# final_sensor_sch.net
KiCad netlist of a schematic drawn in Altium Designer
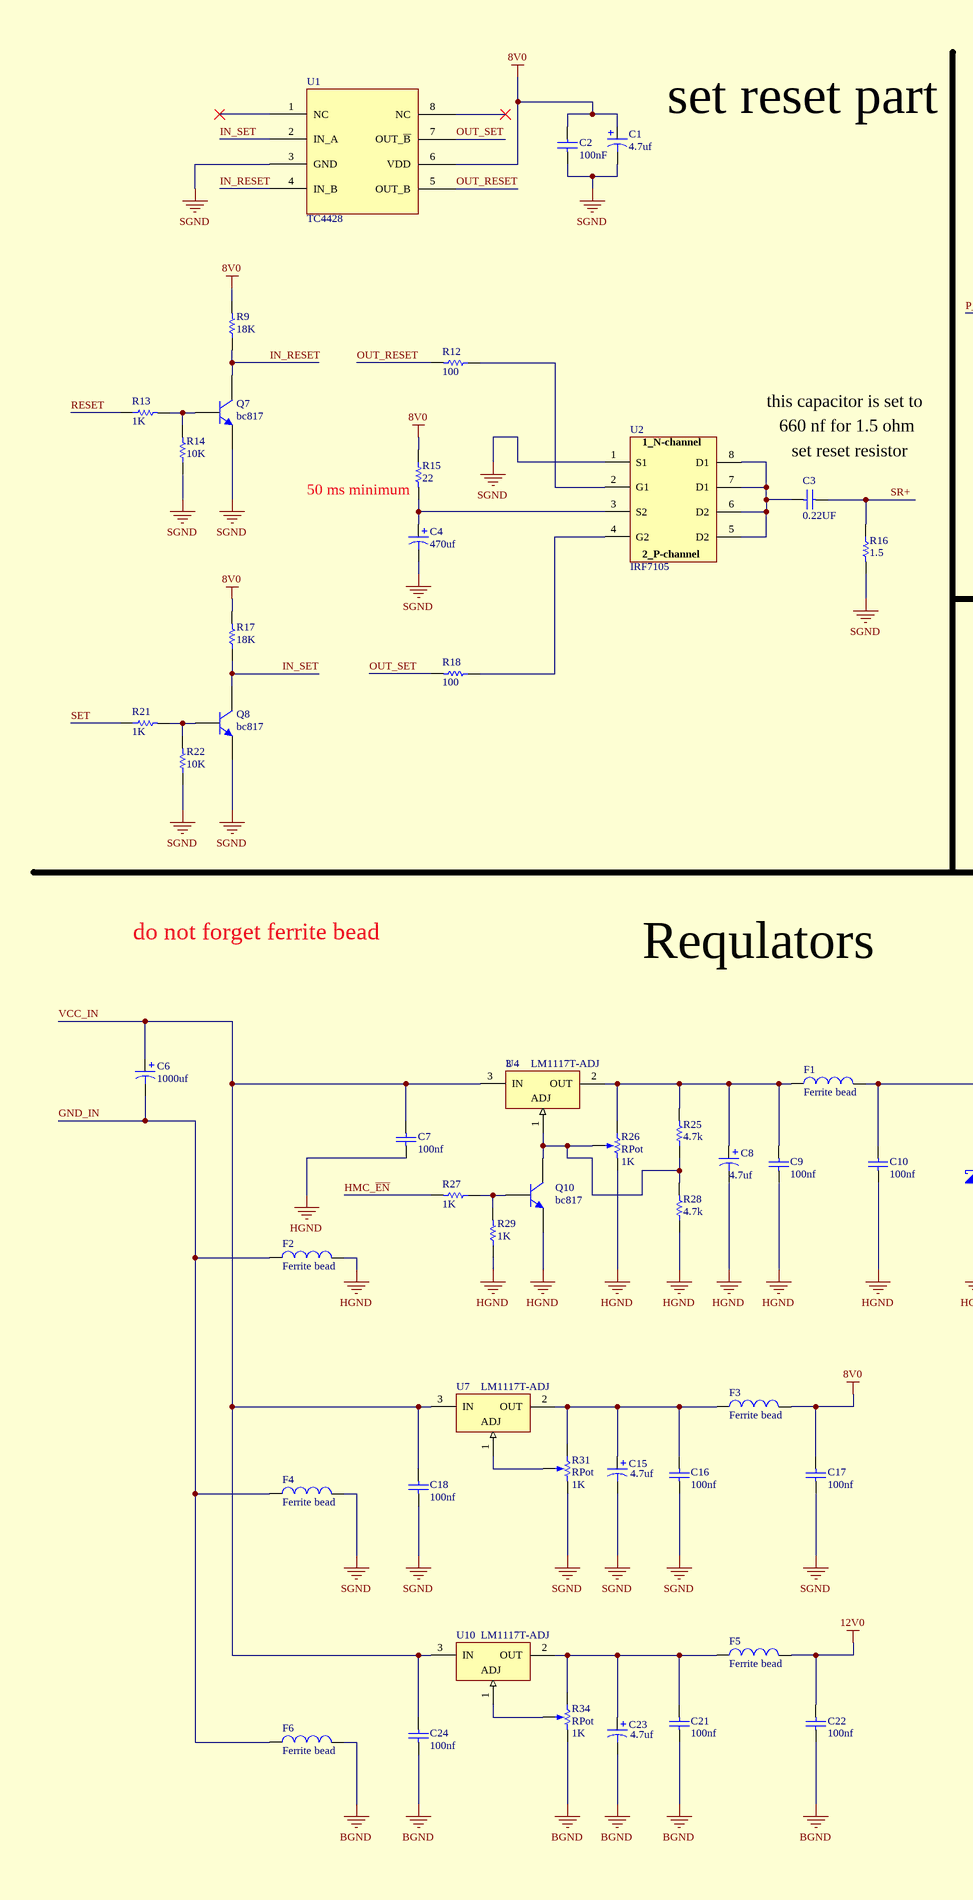
[diagram p0: final_sensor_sch.SchDoc, left]
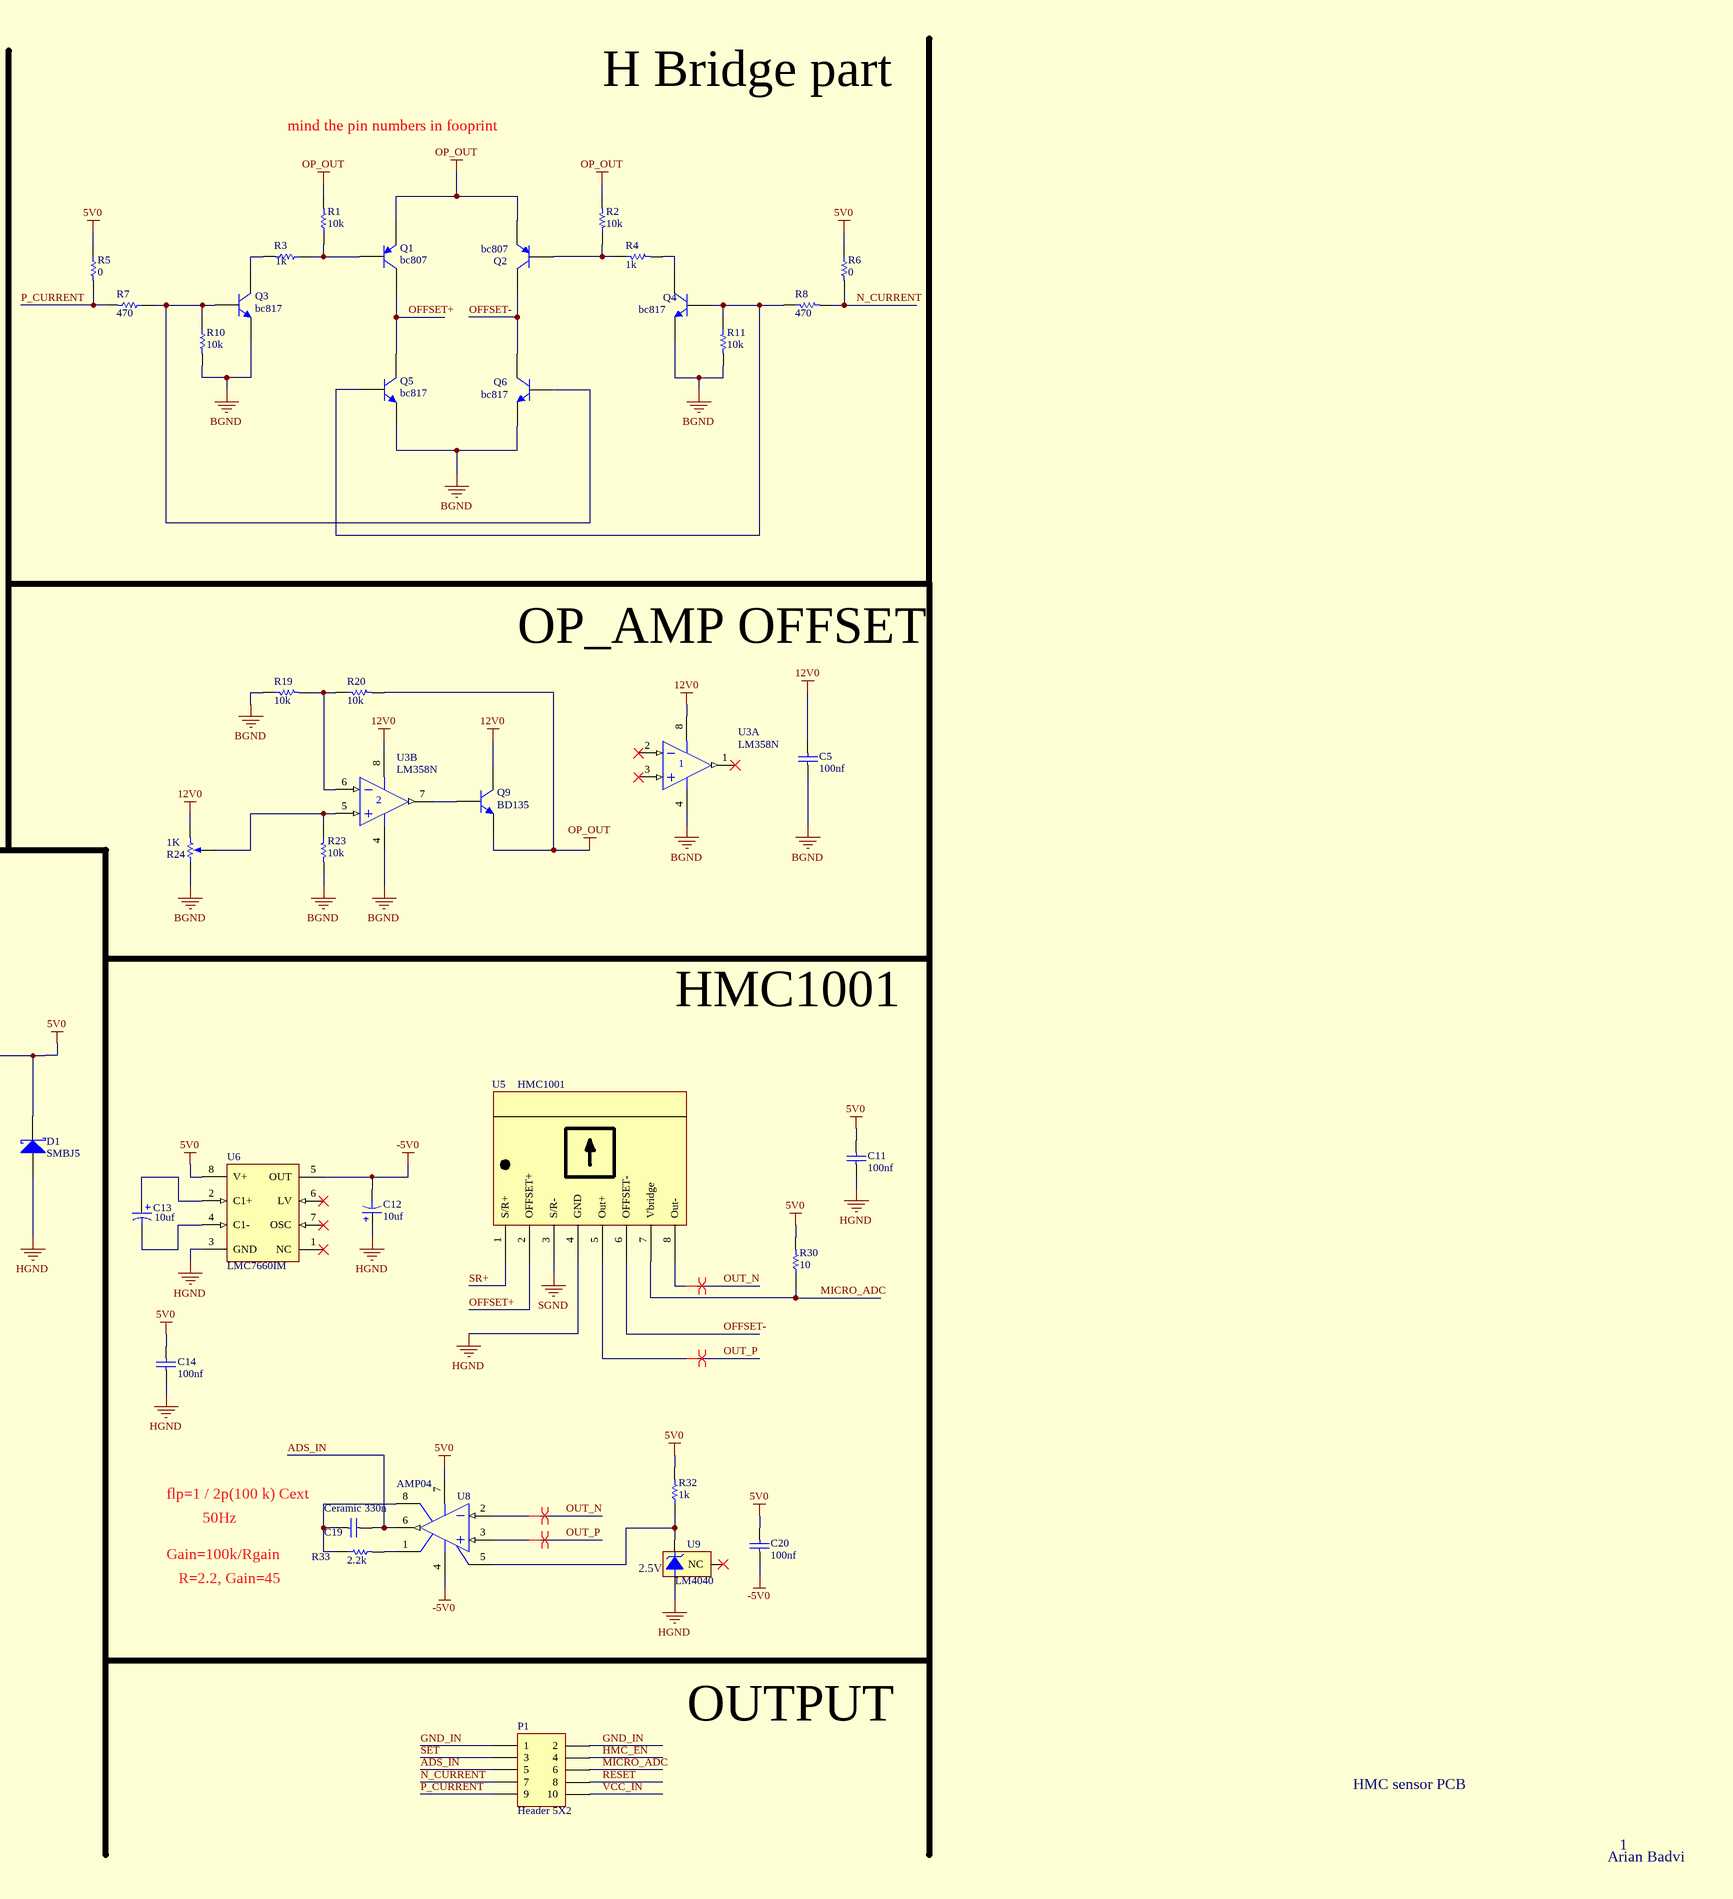
[diagram p1: final_sensor_sch.SchDoc, right]

(export (version "E")
  (design (tool "Eeschema 10.0.6"))
  (components
    (comp (ref "C1")
      (value "4.7uf")
      (footprint "cap_smd_a")
      (description "Polarized Capacitor (Radial)")
      (fields (field (name "PUBLISHER") "Altium Limited"))
      (libsource (lib "") (part "Cap Pol1_1"))
    )
    (comp (ref "C2")
      (value "100nF")
      (footprint "1206")
      (description "Capacitor")
      (fields (field (name "PUBLISHER") "Altium Limited"))
      (libsource (lib "Miscellaneous Devices") (part "Cap"))
    )
    (comp (ref "C3")
      (value "0.22UF")
      (footprint "1206")
      (description "Capacitor")
      (fields (field (name "PUBLISHER") "Altium Limited"))
      (libsource (lib "Miscellaneous Devices") (part "Cap"))
    )
    (comp (ref "C4")
      (value "470uf")
      (footprint "cap_smd_d")
      (description "Polarized Capacitor (Radial)")
      (fields (field (name "PUBLISHER") "Altium Limited"))
      (libsource (lib "Miscellaneous Devices") (part "Cap Pol1"))
    )
    (comp (ref "C5")
      (value "100nf")
      (footprint "1206")
      (description "Capacitor")
      (fields (field (name "PUBLISHER") "Altium Limited"))
      (libsource (lib "Miscellaneous Devices") (part "Cap"))
    )
    (comp (ref "C6")
      (value "1000uf")
      (footprint "c_cyl_smd")
      (description "electrolytic smd cap")
      (fields (field (name "PUBLISHER") "Altium Limited"))
      (libsource (lib "Miscellaneous Devices") (part "Cap Pol1"))
    )
    (comp (ref "C7")
      (value "100nf")
      (footprint "1206")
      (description "Capacitor")
      (fields (field (name "PUBLISHER") "Altium Limited"))
      (libsource (lib "Miscellaneous Devices") (part "Cap"))
    )
    (comp (ref "C8")
      (value "4.7uf")
      (footprint "cap_smd_a")
      (description "Polarized Capacitor (Radial)")
      (fields (field (name "PUBLISHER") "Altium Limited"))
      (libsource (lib "Miscellaneous Devices") (part "Cap Pol1"))
    )
    (comp (ref "C9")
      (value "100nf")
      (footprint "1206")
      (description "Capacitor")
      (fields (field (name "PUBLISHER") "Altium Limited"))
      (libsource (lib "Miscellaneous Devices") (part "Cap"))
    )
    (comp (ref "C10")
      (value "100nf")
      (footprint "1206")
      (description "Capacitor")
      (fields (field (name "PUBLISHER") "Altium Limited"))
      (libsource (lib "Miscellaneous Devices") (part "Cap"))
    )
    (comp (ref "C11")
      (value "100nf")
      (footprint "1206")
      (description "Capacitor")
      (fields (field (name "PUBLISHER") "Altium Limited"))
      (libsource (lib "Miscellaneous Devices") (part "Cap"))
    )
    (comp (ref "C12")
      (value "10uf")
      (footprint "cap_smd_a")
      (description "Polarized Capacitor (Radial)")
      (fields (field (name "PUBLISHER") "Altium Limited"))
      (libsource (lib "Miscellaneous Devices") (part "Cap Pol1"))
    )
    (comp (ref "C13")
      (value "10uf")
      (footprint "cap_smd_a")
      (description "Polarized Capacitor (Radial)")
      (fields (field (name "PUBLISHER") "Altium Limited"))
      (libsource (lib "Miscellaneous Devices") (part "Cap Pol1"))
    )
    (comp (ref "C14")
      (value "100nf")
      (footprint "1206")
      (description "Capacitor")
      (fields (field (name "PUBLISHER") "Altium Limited"))
      (libsource (lib "Miscellaneous Devices") (part "Cap"))
    )
    (comp (ref "C15")
      (value "4.7uf")
      (footprint "cap_smd_a")
      (description "Polarized Capacitor (Radial)")
      (fields (field (name "PUBLISHER") "Altium Limited"))
      (libsource (lib "Miscellaneous Devices") (part "Cap Pol1"))
    )
    (comp (ref "C16")
      (value "100nf")
      (footprint "1206")
      (description "Capacitor")
      (fields (field (name "PUBLISHER") "Altium Limited"))
      (libsource (lib "Miscellaneous Devices") (part "Cap"))
    )
    (comp (ref "C17")
      (value "100nf")
      (footprint "1206")
      (description "Capacitor")
      (fields (field (name "PUBLISHER") "Altium Limited"))
      (libsource (lib "Miscellaneous Devices") (part "Cap"))
    )
    (comp (ref "C18")
      (value "100nf")
      (footprint "1206")
      (description "Capacitor")
      (fields (field (name "PUBLISHER") "Altium Limited"))
      (libsource (lib "Miscellaneous Devices") (part "Cap"))
    )
    (comp (ref "C19")
      (value "Ceramic 330n")
      (footprint "1206")
      (description "Capacitor")
      (fields (field (name "PUBLISHER") "Altium Limited"))
      (libsource (lib "Library") (part "Cap"))
    )
    (comp (ref "C20")
      (value "100nf")
      (footprint "1206")
      (description "Capacitor")
      (fields (field (name "PUBLISHER") "Altium Limited"))
      (libsource (lib "Miscellaneous Devices") (part "Cap"))
    )
    (comp (ref "C21")
      (value "100nf")
      (footprint "1206")
      (description "Capacitor")
      (fields (field (name "PUBLISHER") "Altium Limited"))
      (libsource (lib "Miscellaneous Devices") (part "Cap"))
    )
    (comp (ref "C22")
      (value "100nf")
      (footprint "1206")
      (description "Capacitor")
      (fields (field (name "PUBLISHER") "Altium Limited"))
      (libsource (lib "Miscellaneous Devices") (part "Cap"))
    )
    (comp (ref "C23")
      (value "4.7uf")
      (footprint "cap_smd_a")
      (description "Polarized Capacitor (Radial)")
      (fields (field (name "PUBLISHER") "Altium Limited"))
      (libsource (lib "Miscellaneous Devices") (part "Cap Pol1"))
    )
    (comp (ref "C24")
      (value "100nf")
      (footprint "1206")
      (description "Capacitor")
      (fields (field (name "PUBLISHER") "Altium Limited"))
      (libsource (lib "Miscellaneous Devices") (part "Cap"))
    )
    (comp (ref "D1")
      (value "SMBJ5")
      (footprint "tvs")
      (description "tvs")
      (fields (field (name "PUBLISHER") "Altium Limited"))
      (libsource (lib "Miscellaneous Devices") (part "Diode 10TQ040"))
    )
    (comp (ref "F1")
      (value "Ferrite bead")
      (footprint "1206")
      (description "Ferrite bead, 1206")
      (fields (field (name "PUBLISHER") "Altium Limited"))
      (libsource (lib "Miscellaneous Devices") (part "Inductor"))
    )
    (comp (ref "F2")
      (value "Ferrite bead")
      (footprint "1206")
      (description "Ferrite bead, 1206")
      (fields (field (name "PUBLISHER") "Altium Limited"))
      (libsource (lib "Miscellaneous Devices") (part "Inductor"))
    )
    (comp (ref "F3")
      (value "Ferrite bead")
      (footprint "1206")
      (description "Ferrite bead, 1206")
      (fields (field (name "PUBLISHER") "Altium Limited"))
      (libsource (lib "Miscellaneous Devices") (part "Inductor"))
    )
    (comp (ref "F4")
      (value "Ferrite bead")
      (footprint "1206")
      (description "Ferrite bead, 1206")
      (fields (field (name "PUBLISHER") "Altium Limited"))
      (libsource (lib "Miscellaneous Devices") (part "Inductor"))
    )
    (comp (ref "F5")
      (value "Ferrite bead")
      (footprint "1206")
      (description "Ferrite bead, 1206")
      (fields (field (name "PUBLISHER") "Altium Limited"))
      (libsource (lib "Miscellaneous Devices") (part "Inductor"))
    )
    (comp (ref "F6")
      (value "Ferrite bead")
      (footprint "1206")
      (description "Ferrite bead, 1206")
      (fields (field (name "PUBLISHER") "Altium Limited"))
      (libsource (lib "Miscellaneous Devices") (part "Inductor"))
    )
    (comp (ref "P1")
      (value "Header 5X2")
      (footprint "HDR2X5")
      (description "Header, 5-Pin, Dual row")
      (fields (field (name "PUBLISHER") "Altium Limited"))
      (libsource (lib "Miscellaneous Connectors") (part "Header 5X2"))
    )
    (comp (ref "Q1")
      (value "bc807")
      (footprint "sot-23")
      (description "PNP General Purpose Amplifier")
      (fields (field (name "PUBLISHER") "Altium Limited"))
      (libsource (lib "Miscellaneous Devices") (part "2N3906"))
    )
    (comp (ref "Q2")
      (value "bc807")
      (footprint "sot-23")
      (description "PNP General Purpose Amplifier")
      (fields (field (name "PUBLISHER") "Altium Limited"))
      (libsource (lib "Miscellaneous Devices") (part "2N3906"))
    )
    (comp (ref "Q3")
      (value "bc817")
      (footprint "sot-23")
      (description "NPN General Purpose Amplifier")
      (fields (field (name "PUBLISHER") "Altium Limited"))
      (libsource (lib "Miscellaneous Devices") (part "2N3904"))
    )
    (comp (ref "Q4")
      (value "bc817")
      (footprint "sot-23")
      (description "NPN General Purpose Amplifier")
      (fields (field (name "PUBLISHER") "Altium Limited"))
      (libsource (lib "Miscellaneous Devices") (part "2N3904"))
    )
    (comp (ref "Q5")
      (value "bc817")
      (footprint "sot-23")
      (description "NPN General Purpose Amplifier")
      (fields (field (name "PUBLISHER") "Altium Limited"))
      (libsource (lib "Miscellaneous Devices") (part "2N3904"))
    )
    (comp (ref "Q6")
      (value "bc817")
      (footprint "sot-23")
      (description "NPN General Purpose Amplifier")
      (fields (field (name "PUBLISHER") "Altium Limited"))
      (libsource (lib "Miscellaneous Devices") (part "2N3904"))
    )
    (comp (ref "Q7")
      (value "bc817")
      (footprint "sot-23")
      (description "NPN General Purpose Amplifier")
      (fields (field (name "PUBLISHER") "Altium Limited"))
      (libsource (lib "Miscellaneous Devices") (part "2N3904"))
    )
    (comp (ref "Q8")
      (value "bc817")
      (footprint "sot-23")
      (description "NPN General Purpose Amplifier")
      (fields (field (name "PUBLISHER") "Altium Limited"))
      (libsource (lib "Miscellaneous Devices") (part "2N3904"))
    )
    (comp (ref "Q9")
      (value "BD135")
      (footprint "sot-32")
      (description "NPN General Purpose Amplifier")
      (fields (field (name "PUBLISHER") "Altium Limited"))
      (libsource (lib "") (part "2N3904_1"))
    )
    (comp (ref "Q10")
      (value "bc817")
      (footprint "sot-23")
      (description "NPN General Purpose Amplifier")
      (fields (field (name "PUBLISHER") "Altium Limited"))
      (libsource (lib "Miscellaneous Devices") (part "2N3904"))
    )
    (comp (ref "R1")
      (value "10k")
      (footprint "1206")
      (description "Resistor")
      (fields (field (name "PUBLISHER") "Altium Limited"))
      (libsource (lib "Miscellaneous Devices") (part "Res1"))
    )
    (comp (ref "R2")
      (value "10k")
      (footprint "1206")
      (description "Resistor")
      (fields (field (name "PUBLISHER") "Altium Limited"))
      (libsource (lib "Miscellaneous Devices") (part "Res1"))
    )
    (comp (ref "R3")
      (value "1k")
      (footprint "1206")
      (description "Resistor")
      (fields (field (name "PUBLISHER") "Altium Limited"))
      (libsource (lib "Miscellaneous Devices") (part "Res1"))
    )
    (comp (ref "R4")
      (value "1k")
      (footprint "1206")
      (description "Resistor")
      (fields (field (name "PUBLISHER") "Altium Limited"))
      (libsource (lib "Miscellaneous Devices") (part "Res1"))
    )
    (comp (ref "R5")
      (value "0")
      (footprint "1206")
      (description "Resistor")
      (fields (field (name "PUBLISHER") "Altium Limited"))
      (libsource (lib "Miscellaneous Devices") (part "Res1"))
    )
    (comp (ref "R6")
      (value "0")
      (footprint "1206")
      (description "Resistor")
      (fields (field (name "PUBLISHER") "Altium Limited"))
      (libsource (lib "Miscellaneous Devices") (part "Res1"))
    )
    (comp (ref "R7")
      (value "470")
      (footprint "1206")
      (description "Resistor")
      (fields (field (name "PUBLISHER") "Altium Limited"))
      (libsource (lib "Miscellaneous Devices") (part "Res1"))
    )
    (comp (ref "R8")
      (value "470")
      (footprint "1206")
      (description "Resistor")
      (fields (field (name "PUBLISHER") "Altium Limited"))
      (libsource (lib "Miscellaneous Devices") (part "Res1"))
    )
    (comp (ref "R9")
      (value "18K")
      (footprint "1206")
      (description "Resistor")
      (fields (field (name "PUBLISHER") "Altium Limited"))
      (libsource (lib "Miscellaneous Devices") (part "Res1"))
    )
    (comp (ref "R10")
      (value "10k")
      (footprint "1206")
      (description "Resistor")
      (fields (field (name "PUBLISHER") "Altium Limited"))
      (libsource (lib "Miscellaneous Devices") (part "Res1"))
    )
    (comp (ref "R11")
      (value "10k")
      (footprint "1206")
      (description "Resistor")
      (fields (field (name "PUBLISHER") "Altium Limited"))
      (libsource (lib "Miscellaneous Devices") (part "Res1"))
    )
    (comp (ref "R12")
      (value "100")
      (footprint "1206")
      (description "Resistor")
      (fields (field (name "PUBLISHER") "Altium Limited"))
      (libsource (lib "Miscellaneous Devices") (part "Res1"))
    )
    (comp (ref "R13")
      (value "1K")
      (footprint "1206")
      (description "Resistor")
      (fields (field (name "PUBLISHER") "Altium Limited"))
      (libsource (lib "Miscellaneous Devices") (part "Res1"))
    )
    (comp (ref "R14")
      (value "10K")
      (footprint "1206")
      (description "Resistor")
      (fields (field (name "PUBLISHER") "Altium Limited"))
      (libsource (lib "Miscellaneous Devices") (part "Res1"))
    )
    (comp (ref "R15")
      (value "22")
      (footprint "1206")
      (description "Resistor")
      (fields (field (name "PUBLISHER") "Altium Limited"))
      (libsource (lib "Miscellaneous Devices") (part "Res1"))
    )
    (comp (ref "R16")
      (value "1.5")
      (footprint "1206")
      (description "Resistor")
      (fields (field (name "PUBLISHER") "Altium Limited"))
      (libsource (lib "Miscellaneous Devices") (part "Res1"))
    )
    (comp (ref "R17")
      (value "18K")
      (footprint "1206")
      (description "Resistor")
      (fields (field (name "PUBLISHER") "Altium Limited"))
      (libsource (lib "Miscellaneous Devices") (part "Res1"))
    )
    (comp (ref "R18")
      (value "100")
      (footprint "1206")
      (description "Resistor")
      (fields (field (name "PUBLISHER") "Altium Limited"))
      (libsource (lib "Miscellaneous Devices") (part "Res1"))
    )
    (comp (ref "R19")
      (value "10k")
      (footprint "1206")
      (description "Resistor")
      (fields (field (name "PUBLISHER") "Altium Limited"))
      (libsource (lib "") (part "Res1_1"))
    )
    (comp (ref "R20")
      (value "10k")
      (footprint "1206")
      (description "Resistor")
      (fields (field (name "PUBLISHER") "Altium Limited"))
      (libsource (lib "") (part "Res1_1"))
    )
    (comp (ref "R21")
      (value "1K")
      (footprint "1206")
      (description "Resistor")
      (fields (field (name "PUBLISHER") "Altium Limited"))
      (libsource (lib "Miscellaneous Devices") (part "Res1"))
    )
    (comp (ref "R22")
      (value "10K")
      (footprint "1206")
      (description "Resistor")
      (fields (field (name "PUBLISHER") "Altium Limited"))
      (libsource (lib "Miscellaneous Devices") (part "Res1"))
    )
    (comp (ref "R23")
      (value "10k")
      (footprint "1206")
      (description "Resistor")
      (fields (field (name "PUBLISHER") "Altium Limited"))
      (libsource (lib "Miscellaneous Devices") (part "Res1"))
    )
    (comp (ref "R24")
      (value "1K")
      (footprint "pot smd")
      (description "Potentiometer")
      (fields (field (name "Comment") "RPot") (field (name "PUBLISHER") "Altium Limited"))
      (libsource (lib "") (part "RPot_1"))
    )
    (comp (ref "R25")
      (value "4.7k")
      (footprint "1206")
      (description "Resistor, 1/4W")
      (fields
        (field (name "Comment") "Resistor")
        (field (name "PUBLISHER") "Seyed Razi Vesali")
        (field (name "EMAIL") "razi.vesali@gmail.com")
      )
      (libsource (lib "resistor1") (part "Resistor"))
    )
    (comp (ref "R26")
      (value "RPot")
      (footprint "pot smd")
      (description "Potentiometer")
      (fields (field (name "ALTIUM_VALUE") "1K") (field (name "PUBLISHER") "Altium Limited"))
      (libsource (lib "") (part "RPot_1"))
    )
    (comp (ref "R27")
      (value "1K")
      (footprint "1206")
      (description "Resistor")
      (fields (field (name "PUBLISHER") "Altium Limited"))
      (libsource (lib "Miscellaneous Devices") (part "Res1"))
    )
    (comp (ref "R28")
      (value "4.7k")
      (footprint "1206")
      (description "Resistor, 1/4W")
      (fields
        (field (name "Comment") "Resistor")
        (field (name "PUBLISHER") "Seyed Razi Vesali")
        (field (name "EMAIL") "razi.vesali@gmail.com")
      )
      (libsource (lib "resistor1") (part "Resistor"))
    )
    (comp (ref "R29")
      (value "1K")
      (footprint "1206")
      (description "Resistor")
      (fields (field (name "PUBLISHER") "Altium Limited"))
      (libsource (lib "Miscellaneous Devices") (part "Res1"))
    )
    (comp (ref "R30")
      (value "10")
      (footprint "1206")
      (description "Resistor, 1/4W")
      (fields
        (field (name "Comment") "Resistor")
        (field (name "PUBLISHER") "Seyed Razi Vesali")
        (field (name "EMAIL") "razi.vesali@gmail.com")
      )
      (libsource (lib "resistor1") (part "Resistor"))
    )
    (comp (ref "R31")
      (value "RPot")
      (footprint "pot smd")
      (description "Potentiometer")
      (fields (field (name "ALTIUM_VALUE") "1K") (field (name "PUBLISHER") "Altium Limited"))
      (libsource (lib "Miscellaneous Devices") (part "RPot"))
    )
    (comp (ref "R32")
      (value "1k")
      (footprint "1206")
      (description "Resistor, 1/4W")
      (fields
        (field (name "Comment") "Resistor")
        (field (name "PUBLISHER") "Seyed Razi Vesali")
        (field (name "EMAIL") "razi.vesali@gmail.com")
      )
      (libsource (lib "resistor1") (part "Resistor"))
    )
    (comp (ref "R33")
      (value "2.2k")
      (footprint "1206")
      (description "General Resistor")
      (fields (field (name "Comment") "Res 3K2") (field (name "PUBLISHER") "Altium Limited"))
      (libsource (lib "Library") (part "Resistor"))
    )
    (comp (ref "R34")
      (value "RPot")
      (footprint "pot smd")
      (description "Potentiometer")
      (fields (field (name "ALTIUM_VALUE") "1K") (field (name "PUBLISHER") "Altium Limited"))
      (libsource (lib "Miscellaneous Devices") (part "RPot"))
    )
    (comp (ref "U1") (value "TC4428") (footprint "sop8") (libsource (lib "tc4428") (part "TC4428")))
    (comp (ref "U2") (value "IRF7105") (footprint "sop8") (libsource (lib "irf7106") (part "IRF7106")))
    (comp (ref "U3")
      (value "LM358N")
      (footprint "sop8")
      (description "Dual Low-Power Operational Amplifier")
      (fields (field (name "PUBLISHER") "Altium Limited"))
      (libsource (lib "Motorola Amplifier Operational Amplifier") (part "LM358N"))
    )
    (comp (ref "U4")
      (value "LM1117T-ADJ")
      (footprint "dpak")
      (description "800mA Low-Dropout Linear Regulator")
      (fields
        (field (name "PINCOUNT") "3")
        (field (name "MANUFACTURER") "National Semiconductor")
        (field (name "DIGIKEYPARTNUMBER") "LM1117T-ADJ-ND")
        (field (name "PUBLISHER") "Altium Limited")
      )
      (libsource (lib "NSC LDO") (part "LM1117T-ADJ"))
    )
    (comp (ref "U5") (value "HMC1001") (footprint "HMC1001") (libsource (lib "Library") (part "HMC1001")))
    (comp (ref "U6")
      (value "LMC7660IM")
      (footprint "sop8")
      (description "Switched Capacitor Voltage Converter")
      (fields
        (field (name "MANUFACTURER") "National Semiconductor")
        (field (name "DIGIKEYPARTNUMBER") "LMC7660IM-ND")
        (field (name "PUBLISHER") "Altium Limited")
      )
      (libsource (lib "NSC Switch Caps") (part "LMC7660IM"))
    )
    (comp (ref "U7")
      (value "LM1117T-ADJ")
      (footprint "dpak")
      (description "800mA Low-Dropout Linear Regulator")
      (fields
        (field (name "MANUFACTURER") "National Semiconductor")
        (field (name "DIGIKEYPARTNUMBER") "LM1117T-ADJ-ND")
        (field (name "PUBLISHER") "Altium Limited")
      )
      (libsource (lib "NSC LDO") (part "LM1117T-ADJ"))
    )
    (comp (ref "U8")
      (value "AMP04")
      (footprint "sop8")
      (fields (field (name "PUBLISHER") "Altium Limited"))
      (libsource (lib "Miscellaneous Devices") (part "Op Amp"))
    )
    (comp (ref "U9")
      (value "LM4040")
      (footprint "sot-23")
      (description "Precision Micropower Shunt Voltage Reference, 3-pin SOT-23")
      (fields
        (field (name "PARTNUMBER") "LM4040DIM3-10.0")
        (field (name "MANUFACTURER") "National Semiconductor")
        (field (name "PUBLISHER") "Altium Limited")
      )
      (libsource (lib "final_sensor_sch_lib") (part "LM4040"))
    )
    (comp (ref "U10")
      (value "LM1117T-ADJ")
      (footprint "dpak")
      (description "800mA Low-Dropout Linear Regulator")
      (fields
        (field (name "MANUFACTURER") "National Semiconductor")
        (field (name "DIGIKEYPARTNUMBER") "LM1117T-ADJ-ND")
        (field (name "PUBLISHER") "Altium Limited")
      )
      (libsource (lib "NSC LDO") (part "LM1117T-ADJ"))
    )
  )
  (nets
    (net (code "1") (name "-5V0") (class "Default")
      (node (ref "C12") (pin "2") (pinfunction "2_2") (pintype "passive"))
      (node (ref "C20") (pin "1") (pinfunction "1_1") (pintype "passive"))
      (node (ref "U6") (pin "5") (pinfunction "OUT_5") (pintype "power_in"))
      (node (ref "U8") (pin "4") (pinfunction "V-_4") (pintype "power_in"))
    )
    (net (code "2") (name "/ADS_IN") (class "Default")
      (node (ref "C19") (pin "1") (pinfunction "1_1") (pintype "passive"))
      (node (ref "P1") (pin "5") (pinfunction "5_5") (pintype "passive"))
      (node (ref "U8") (pin "6") (pinfunction "OUT_6") (pintype "output"))
    )
    (net (code "3") (name "/GND_IN") (class "Default")
      (node (ref "C6") (pin "2") (pinfunction "2_2") (pintype "passive"))
      (node (ref "F2") (pin "1") (pinfunction "1_1") (pintype "passive"))
      (node (ref "F4") (pin "1") (pinfunction "1_1") (pintype "passive"))
      (node (ref "F6") (pin "1") (pinfunction "1_1") (pintype "passive"))
      (node (ref "P1") (pin "1") (pinfunction "1_1") (pintype "passive"))
      (node (ref "P1") (pin "2") (pinfunction "2_2") (pintype "passive"))
    )
    (net (code "4") (name "/HMC_~{EN}") (class "Default")
      (node (ref "P1") (pin "4") (pinfunction "4_4") (pintype "passive"))
      (node (ref "R27") (pin "2") (pinfunction "2_2") (pintype "passive"))
    )
    (net (code "5") (name "/IN_RESET") (class "Default")
      (node (ref "Q7") (pin "3") (pinfunction "C_3") (pintype "passive"))
      (node (ref "R9") (pin "1") (pinfunction "1_1") (pintype "passive"))
      (node (ref "U1") (pin "4") (pinfunction "IN_B_4") (pintype "passive"))
    )
    (net (code "6") (name "/IN_SET") (class "Default")
      (node (ref "Q8") (pin "3") (pinfunction "C_3") (pintype "passive"))
      (node (ref "R17") (pin "1") (pinfunction "1_1") (pintype "passive"))
      (node (ref "U1") (pin "2") (pinfunction "IN_A_2") (pintype "passive"))
    )
    (net (code "7") (name "/MICRO_ADC") (class "Default")
      (node (ref "P1") (pin "6") (pinfunction "6_6") (pintype "passive"))
      (node (ref "R30") (pin "1") (pinfunction "1_1") (pintype "passive"))
      (node (ref "U5") (pin "7") (pinfunction "Vbridge_7") (pintype "passive"))
    )
    (net (code "8") (name "/N_CURRENT") (class "Default")
      (node (ref "P1") (pin "7") (pinfunction "7_7") (pintype "passive"))
      (node (ref "R6") (pin "2") (pinfunction "2_2") (pintype "passive"))
      (node (ref "R8") (pin "2") (pinfunction "2_2") (pintype "passive"))
    )
    (net (code "9") (name "/OFFSET+") (class "Default")
      (node (ref "Q1") (pin "3") (pinfunction "C_3") (pintype "passive"))
      (node (ref "Q5") (pin "3") (pinfunction "C_3") (pintype "passive"))
      (node (ref "U5") (pin "2") (pinfunction "OFFSET+_2") (pintype "passive"))
    )
    (net (code "10") (name "/OFFSET-") (class "Default")
      (node (ref "Q2") (pin "3") (pinfunction "C_3") (pintype "passive"))
      (node (ref "Q6") (pin "3") (pinfunction "C_3") (pintype "passive"))
      (node (ref "U5") (pin "6") (pinfunction "OFFSET-_6") (pintype "passive"))
    )
    (net (code "11") (name "/OUT_N") (class "Default")
      (node (ref "U5") (pin "8") (pinfunction "Out-_8") (pintype "passive"))
      (node (ref "U8") (pin "2") (pinfunction "IN-_2") (pintype "input"))
    )
    (net (code "12") (name "/OUT_P") (class "Default")
      (node (ref "U5") (pin "5") (pinfunction "Out+_5") (pintype "passive"))
      (node (ref "U8") (pin "3") (pinfunction "IN+_3") (pintype "input"))
    )
    (net (code "13") (name "/OUT_RESET") (class "Default")
      (node (ref "R12") (pin "2") (pinfunction "2_2") (pintype "passive"))
      (node (ref "U1") (pin "5") (pinfunction "OUT_B_5") (pintype "passive"))
    )
    (net (code "14") (name "/OUT_SET") (class "Default")
      (node (ref "R18") (pin "2") (pinfunction "2_2") (pintype "passive"))
      (node (ref "U1") (pin "7") (pinfunction "OUT_~{B}_7") (pintype "passive"))
    )
    (net (code "15") (name "/P_CURRENT") (class "Default")
      (node (ref "P1") (pin "9") (pinfunction "9_9") (pintype "passive"))
      (node (ref "R5") (pin "2") (pinfunction "2_2") (pintype "passive"))
      (node (ref "R7") (pin "2") (pinfunction "2_2") (pintype "passive"))
    )
    (net (code "16") (name "/RESET") (class "Default")
      (node (ref "P1") (pin "8") (pinfunction "8_8") (pintype "passive"))
      (node (ref "R13") (pin "1") (pinfunction "1_1") (pintype "passive"))
    )
    (net (code "17") (name "/SET") (class "Default")
      (node (ref "P1") (pin "3") (pinfunction "3_3") (pintype "passive"))
      (node (ref "R21") (pin "1") (pinfunction "1_1") (pintype "passive"))
    )
    (net (code "18") (name "/SR+") (class "Default")
      (node (ref "C3") (pin "2") (pinfunction "2_2") (pintype "passive"))
      (node (ref "R16") (pin "1") (pinfunction "1_1") (pintype "passive"))
      (node (ref "U5") (pin "1") (pinfunction "S/R+_1") (pintype "passive"))
    )
    (net (code "19") (name "/VCC_IN") (class "Default")
      (node (ref "C18") (pin "2") (pinfunction "2_2") (pintype "passive"))
      (node (ref "C24") (pin "2") (pinfunction "2_2") (pintype "passive"))
      (node (ref "C6") (pin "1") (pinfunction "1_1") (pintype "passive"))
      (node (ref "C7") (pin "2") (pinfunction "2_2") (pintype "passive"))
      (node (ref "P1") (pin "10") (pinfunction "10_10") (pintype "passive"))
      (node (ref "U10") (pin "3") (pinfunction "IN_3") (pintype "power_in"))
      (node (ref "U4") (pin "3") (pinfunction "IN_3") (pintype "power_in"))
      (node (ref "U7") (pin "3") (pinfunction "IN_3") (pintype "power_in"))
    )
    (net (code "20") (name "5V0") (class "Default")
      (node (ref "C10") (pin "2") (pinfunction "2_2") (pintype "passive"))
      (node (ref "C11") (pin "2") (pinfunction "2_2") (pintype "passive"))
      (node (ref "C14") (pin "2") (pinfunction "2_2") (pintype "passive"))
      (node (ref "C20") (pin "2") (pinfunction "2_2") (pintype "passive"))
      (node (ref "D1") (pin "2") (pinfunction "K_2") (pintype "passive"))
      (node (ref "F1") (pin "2") (pinfunction "2_2") (pintype "passive"))
      (node (ref "R30") (pin "2") (pinfunction "2_2") (pintype "passive"))
      (node (ref "R32") (pin "2") (pinfunction "2_2") (pintype "passive"))
      (node (ref "R5") (pin "1") (pinfunction "1_1") (pintype "passive"))
      (node (ref "R6") (pin "1") (pinfunction "1_1") (pintype "passive"))
      (node (ref "U6") (pin "8") (pinfunction "V+_8") (pintype "power_in"))
      (node (ref "U8") (pin "7") (pinfunction "V+_7") (pintype "power_in"))
    )
    (net (code "21") (name "8V0") (class "Default")
      (node (ref "C1") (pin "1") (pinfunction "1_1") (pintype "passive"))
      (node (ref "C17") (pin "2") (pinfunction "2_2") (pintype "passive"))
      (node (ref "C2") (pin "1") (pinfunction "1_1") (pintype "passive"))
      (node (ref "F3") (pin "2") (pinfunction "2_2") (pintype "passive"))
      (node (ref "R15") (pin "1") (pinfunction "1_1") (pintype "passive"))
      (node (ref "R17") (pin "2") (pinfunction "2_2") (pintype "passive"))
      (node (ref "R9") (pin "2") (pinfunction "2_2") (pintype "passive"))
      (node (ref "U1") (pin "6") (pinfunction "VDD_6") (pintype "passive"))
    )
    (net (code "22") (name "12V0") (class "Default")
      (node (ref "C22") (pin "2") (pinfunction "2_2") (pintype "passive"))
      (node (ref "C5") (pin "2") (pinfunction "2_2") (pintype "passive"))
      (node (ref "F5") (pin "2") (pinfunction "2_2") (pintype "passive"))
      (node (ref "Q9") (pin "2") (pinfunction "C_2") (pintype "passive"))
      (node (ref "R24") (pin "3") (pinfunction "BOT_3") (pintype "passive"))
      (node (ref "U3") (pin "8") (pinfunction "V+_8") (pintype "power_in"))
    )
    (net (code "23") (name "BGND") (class "Default")
      (node (ref "C21") (pin "1") (pinfunction "1_1") (pintype "passive"))
      (node (ref "C22") (pin "1") (pinfunction "1_1") (pintype "passive"))
      (node (ref "C23") (pin "2") (pinfunction "2_2") (pintype "passive"))
      (node (ref "C24") (pin "1") (pinfunction "1_1") (pintype "passive"))
      (node (ref "C5") (pin "1") (pinfunction "1_1") (pintype "passive"))
      (node (ref "F6") (pin "2") (pinfunction "2_2") (pintype "passive"))
      (node (ref "Q3") (pin "2") (pinfunction "E_2") (pintype "passive"))
      (node (ref "Q4") (pin "2") (pinfunction "E_2") (pintype "passive"))
      (node (ref "Q5") (pin "2") (pinfunction "E_2") (pintype "passive"))
      (node (ref "Q6") (pin "2") (pinfunction "E_2") (pintype "passive"))
      (node (ref "R10") (pin "2") (pinfunction "2_2") (pintype "passive"))
      (node (ref "R11") (pin "2") (pinfunction "2_2") (pintype "passive"))
      (node (ref "R19") (pin "1") (pinfunction "1_1") (pintype "passive"))
      (node (ref "R23") (pin "2") (pinfunction "2_2") (pintype "passive"))
      (node (ref "R24") (pin "1") (pinfunction "TOP_1") (pintype "passive"))
      (node (ref "R34") (pin "2") (pinfunction "BOT_2") (pintype "passive"))
      (node (ref "U3") (pin "4") (pinfunction "V-_4") (pintype "power_in"))
    )
    (net (code "24") (name "HGND") (class "Default")
      (node (ref "C10") (pin "1") (pinfunction "1_1") (pintype "passive"))
      (node (ref "C11") (pin "1") (pinfunction "1_1") (pintype "passive"))
      (node (ref "C12") (pin "1") (pinfunction "1_1") (pintype "passive"))
      (node (ref "C14") (pin "1") (pinfunction "1_1") (pintype "passive"))
      (node (ref "C7") (pin "1") (pinfunction "1_1") (pintype "passive"))
      (node (ref "C8") (pin "2") (pinfunction "2_2") (pintype "passive"))
      (node (ref "C9") (pin "1") (pinfunction "1_1") (pintype "passive"))
      (node (ref "D1") (pin "1") (pinfunction "A_1") (pintype "passive"))
      (node (ref "F2") (pin "2") (pinfunction "2_2") (pintype "passive"))
      (node (ref "Q10") (pin "2") (pinfunction "E_2") (pintype "passive"))
      (node (ref "R26") (pin "3") (pinfunction "BOT_3") (pintype "passive"))
      (node (ref "R28") (pin "1") (pinfunction "1_1") (pintype "passive"))
      (node (ref "R29") (pin "1") (pinfunction "1_1") (pintype "passive"))
      (node (ref "U5") (pin "4") (pinfunction "GND_4") (pintype "passive"))
      (node (ref "U6") (pin "3") (pinfunction "GND_3") (pintype "power_in"))
      (node (ref "U9") (pin "2") (pinfunction "-V_2") (pintype "passive"))
    )
    (net (code "25") (name "Net-(C3-Pad1)") (class "Default")
      (node (ref "C3") (pin "1") (pinfunction "1_1") (pintype "passive"))
      (node (ref "U2") (pin "5") (pinfunction "D2_5") (pintype "passive"))
      (node (ref "U2") (pin "6") (pinfunction "D2_6") (pintype "passive"))
      (node (ref "U2") (pin "7") (pinfunction "D1_7") (pintype "passive"))
      (node (ref "U2") (pin "8") (pinfunction "D1_8") (pintype "passive"))
    )
    (net (code "26") (name "Net-(Q1-B)") (class "Default")
      (node (ref "Q1") (pin "1") (pinfunction "B_1") (pintype "passive"))
      (node (ref "R1") (pin "1") (pinfunction "1_1") (pintype "passive"))
      (node (ref "R3") (pin "1") (pinfunction "1_1") (pintype "passive"))
    )
    (net (code "27") (name "Net-(Q2-B)") (class "Default")
      (node (ref "Q2") (pin "1") (pinfunction "B_1") (pintype "passive"))
      (node (ref "R2") (pin "1") (pinfunction "1_1") (pintype "passive"))
      (node (ref "R4") (pin "1") (pinfunction "1_1") (pintype "passive"))
    )
    (net (code "28") (name "Net-(Q3-B)") (class "Default")
      (node (ref "Q3") (pin "1") (pinfunction "B_1") (pintype "passive"))
      (node (ref "Q6") (pin "1") (pinfunction "B_1") (pintype "passive"))
      (node (ref "R10") (pin "1") (pinfunction "1_1") (pintype "passive"))
      (node (ref "R7") (pin "1") (pinfunction "1_1") (pintype "passive"))
    )
    (net (code "29") (name "Net-(Q3-C)") (class "Default")
      (node (ref "Q3") (pin "3") (pinfunction "C_3") (pintype "passive"))
      (node (ref "R3") (pin "2") (pinfunction "2_2") (pintype "passive"))
    )
    (net (code "30") (name "Net-(Q4-B)") (class "Default")
      (node (ref "Q4") (pin "1") (pinfunction "B_1") (pintype "passive"))
      (node (ref "Q5") (pin "1") (pinfunction "B_1") (pintype "passive"))
      (node (ref "R11") (pin "1") (pinfunction "1_1") (pintype "passive"))
      (node (ref "R8") (pin "1") (pinfunction "1_1") (pintype "passive"))
    )
    (net (code "31") (name "Net-(Q4-C)") (class "Default")
      (node (ref "Q4") (pin "3") (pinfunction "C_3") (pintype "passive"))
      (node (ref "R4") (pin "2") (pinfunction "2_2") (pintype "passive"))
    )
    (net (code "32") (name "Net-(Q7-B)") (class "Default")
      (node (ref "Q7") (pin "1") (pinfunction "B_1") (pintype "passive"))
      (node (ref "R13") (pin "2") (pinfunction "2_2") (pintype "passive"))
      (node (ref "R14") (pin "2") (pinfunction "2_2") (pintype "passive"))
    )
    (net (code "33") (name "Net-(Q8-B)") (class "Default")
      (node (ref "Q8") (pin "1") (pinfunction "B_1") (pintype "passive"))
      (node (ref "R21") (pin "2") (pinfunction "2_2") (pintype "passive"))
      (node (ref "R22") (pin "2") (pinfunction "2_2") (pintype "passive"))
    )
    (net (code "34") (name "Net-(Q9-B)") (class "Default")
      (node (ref "Q9") (pin "1") (pinfunction "B_1") (pintype "passive"))
      (node (ref "U3") (pin "7") (pinfunction "OUT_7") (pintype "output"))
    )
    (net (code "35") (name "Net-(Q10-B)") (class "Default")
      (node (ref "Q10") (pin "1") (pinfunction "B_1") (pintype "passive"))
      (node (ref "R27") (pin "1") (pinfunction "1_1") (pintype "passive"))
      (node (ref "R29") (pin "2") (pinfunction "2_2") (pintype "passive"))
    )
    (net (code "36") (name "Net-(Q10-C)") (class "Default")
      (node (ref "Q10") (pin "3") (pinfunction "C_3") (pintype "passive"))
      (node (ref "R25") (pin "1") (pinfunction "1_1") (pintype "passive"))
      (node (ref "R26") (pin "2") (pinfunction "TAP_2") (pintype "passive"))
      (node (ref "R28") (pin "2") (pinfunction "2_2") (pintype "passive"))
      (node (ref "U4") (pin "1") (pinfunction "ADJ_1") (pintype "input"))
    )
    (net (code "37") (name "Net-(R24-TAP)") (class "Default")
      (node (ref "R23") (pin "1") (pinfunction "1_1") (pintype "passive"))
      (node (ref "R24") (pin "2") (pinfunction "TAP_2") (pintype "passive"))
      (node (ref "U3") (pin "5") (pinfunction "IN+_5") (pintype "input"))
    )
    (net (code "38") (name "Net-(R26-TOP)") (class "Default")
      (node (ref "C8") (pin "1") (pinfunction "1_1") (pintype "passive"))
      (node (ref "C9") (pin "2") (pinfunction "2_2") (pintype "passive"))
      (node (ref "F1") (pin "1") (pinfunction "1_1") (pintype "passive"))
      (node (ref "R25") (pin "2") (pinfunction "2_2") (pintype "passive"))
      (node (ref "R26") (pin "1") (pinfunction "TOP_1") (pintype "passive"))
      (node (ref "U4") (pin "2") (pinfunction "OUT_2") (pintype "power_in"))
    )
    (net (code "39") (name "Net-(R31-TAP)") (class "Default")
      (node (ref "R31") (pin "3") (pinfunction "TAP_3") (pintype "passive"))
      (node (ref "U7") (pin "1") (pinfunction "ADJ_1") (pintype "input"))
    )
    (net (code "40") (name "Net-(R31-TOP)") (class "Default")
      (node (ref "C15") (pin "1") (pinfunction "1_1") (pintype "passive"))
      (node (ref "C16") (pin "2") (pinfunction "2_2") (pintype "passive"))
      (node (ref "F3") (pin "1") (pinfunction "1_1") (pintype "passive"))
      (node (ref "R31") (pin "1") (pinfunction "TOP_1") (pintype "passive"))
      (node (ref "U7") (pin "2") (pinfunction "OUT_2") (pintype "power_in"))
    )
    (net (code "41") (name "Net-(R33-Pad2)") (class "Default")
      (node (ref "R33") (pin "2") (pinfunction "2_2") (pintype "passive"))
      (node (ref "U8") (pin "1") (pinfunction "OS_NUL_1") (pintype "passive"))
    )
    (net (code "42") (name "Net-(R34-TAP)") (class "Default")
      (node (ref "R34") (pin "3") (pinfunction "TAP_3") (pintype "passive"))
      (node (ref "U10") (pin "1") (pinfunction "ADJ_1") (pintype "input"))
    )
    (net (code "43") (name "Net-(R34-TOP)") (class "Default")
      (node (ref "C21") (pin "2") (pinfunction "2_2") (pintype "passive"))
      (node (ref "C23") (pin "1") (pinfunction "1_1") (pintype "passive"))
      (node (ref "F5") (pin "1") (pinfunction "1_1") (pintype "passive"))
      (node (ref "R34") (pin "1") (pinfunction "TOP_1") (pintype "passive"))
      (node (ref "U10") (pin "2") (pinfunction "OUT_2") (pintype "power_in"))
    )
    (net (code "44") (name "Net-(U2-G1)") (class "Default")
      (node (ref "R12") (pin "1") (pinfunction "1_1") (pintype "passive"))
      (node (ref "U2") (pin "2") (pinfunction "G1_2") (pintype "passive"))
    )
    (net (code "45") (name "Net-(U2-G2)") (class "Default")
      (node (ref "R18") (pin "1") (pinfunction "1_1") (pintype "passive"))
      (node (ref "U2") (pin "4") (pinfunction "G2_4") (pintype "passive"))
    )
    (net (code "46") (name "Net-(U2-S2)") (class "Default")
      (node (ref "C4") (pin "1") (pinfunction "1_1") (pintype "passive"))
      (node (ref "R15") (pin "2") (pinfunction "2_2") (pintype "passive"))
      (node (ref "U2") (pin "3") (pinfunction "S2_3") (pintype "passive"))
    )
    (net (code "47") (name "Net-(U3B-IN-)") (class "Default")
      (node (ref "R19") (pin "2") (pinfunction "2_2") (pintype "passive"))
      (node (ref "R20") (pin "1") (pinfunction "1_1") (pintype "passive"))
      (node (ref "U3") (pin "6") (pinfunction "IN-_6") (pintype "input"))
    )
    (net (code "48") (name "Net-(U6-C1+)") (class "Default")
      (node (ref "C13") (pin "1") (pinfunction "1_1") (pintype "passive"))
      (node (ref "U6") (pin "2") (pinfunction "C1+_2") (pintype "input"))
    )
    (net (code "49") (name "Net-(U6-C1-)") (class "Default")
      (node (ref "C13") (pin "2") (pinfunction "2_2") (pintype "passive"))
      (node (ref "U6") (pin "4") (pinfunction "C1-_4") (pintype "input"))
    )
    (net (code "50") (name "Net-(U8-TAB)") (class "Default")
      (node (ref "C19") (pin "2") (pinfunction "2_2") (pintype "passive"))
      (node (ref "R33") (pin "1") (pinfunction "1_1") (pintype "passive"))
      (node (ref "U8") (pin "8") (pinfunction "TAB_8") (pintype "passive"))
    )
    (net (code "51") (name "Net-(U9-+V)") (class "Default")
      (node (ref "R32") (pin "1") (pinfunction "1_1") (pintype "passive"))
      (node (ref "U8") (pin "5") (pinfunction "OS_NUL_5") (pintype "passive"))
      (node (ref "U9") (pin "1") (pinfunction "+V_1") (pintype "passive"))
    )
    (net (code "52") (name "OP_OUT") (class "Default")
      (node (ref "Q1") (pin "2") (pinfunction "E_2") (pintype "passive"))
      (node (ref "Q2") (pin "2") (pinfunction "E_2") (pintype "passive"))
      (node (ref "Q9") (pin "3") (pinfunction "E_3") (pintype "passive"))
      (node (ref "R1") (pin "2") (pinfunction "2_2") (pintype "passive"))
      (node (ref "R2") (pin "2") (pinfunction "2_2") (pintype "passive"))
      (node (ref "R20") (pin "2") (pinfunction "2_2") (pintype "passive"))
    )
    (net (code "53") (name "SGND") (class "Default")
      (node (ref "C1") (pin "2") (pinfunction "2_2") (pintype "passive"))
      (node (ref "C15") (pin "2") (pinfunction "2_2") (pintype "passive"))
      (node (ref "C16") (pin "1") (pinfunction "1_1") (pintype "passive"))
      (node (ref "C17") (pin "1") (pinfunction "1_1") (pintype "passive"))
      (node (ref "C18") (pin "1") (pinfunction "1_1") (pintype "passive"))
      (node (ref "C2") (pin "2") (pinfunction "2_2") (pintype "passive"))
      (node (ref "C4") (pin "2") (pinfunction "2_2") (pintype "passive"))
      (node (ref "F4") (pin "2") (pinfunction "2_2") (pintype "passive"))
      (node (ref "Q7") (pin "2") (pinfunction "E_2") (pintype "passive"))
      (node (ref "Q8") (pin "2") (pinfunction "E_2") (pintype "passive"))
      (node (ref "R14") (pin "1") (pinfunction "1_1") (pintype "passive"))
      (node (ref "R16") (pin "2") (pinfunction "2_2") (pintype "passive"))
      (node (ref "R22") (pin "1") (pinfunction "1_1") (pintype "passive"))
      (node (ref "R31") (pin "2") (pinfunction "BOT_2") (pintype "passive"))
      (node (ref "U1") (pin "3") (pinfunction "GND_3") (pintype "passive"))
      (node (ref "U2") (pin "1") (pinfunction "S1_1") (pintype "passive"))
      (node (ref "U5") (pin "3") (pinfunction "S/R-_3") (pintype "passive"))
    )
    (net (code "54") (name "unconnected-(U1-NC-Pad1)") (class "Default")
      (node (ref "U1") (pin "1") (pinfunction "NC_1") (pintype "passive+no_connect"))
    )
    (net (code "55") (name "unconnected-(U1-NC-Pad8)") (class "Default")
      (node (ref "U1") (pin "8") (pinfunction "NC_8") (pintype "passive+no_connect"))
    )
    (net (code "56") (name "unconnected-(U3A-IN+-Pad3)") (class "Default")
      (node (ref "U3") (pin "3") (pinfunction "IN+_3") (pintype "input+no_connect"))
    )
    (net (code "57") (name "unconnected-(U3A-IN--Pad2)") (class "Default")
      (node (ref "U3") (pin "2") (pinfunction "IN-_2") (pintype "input+no_connect"))
    )
    (net (code "58") (name "unconnected-(U3A-OUT-Pad1)") (class "Default")
      (node (ref "U3") (pin "1") (pinfunction "OUT_1") (pintype "output+no_connect"))
    )
    (net (code "59") (name "unconnected-(U6-LV-Pad6)") (class "Default")
      (node (ref "U6") (pin "6") (pinfunction "LV_6") (pintype "input+no_connect"))
    )
    (net (code "60") (name "unconnected-(U6-NC-Pad1)") (class "Default")
      (node (ref "U6") (pin "1") (pinfunction "NC_1") (pintype "passive+no_connect"))
    )
    (net (code "61") (name "unconnected-(U6-OSC-Pad7)") (class "Default")
      (node (ref "U6") (pin "7") (pinfunction "OSC_7") (pintype "input+no_connect"))
    )
    (net (code "62") (name "unconnected-(U9-NC-Pad3)") (class "Default")
      (node (ref "U9") (pin "3") (pinfunction "NC_3") (pintype "passive+no_connect"))
    )
  )
)
